# USB_Interlock_V3.net
KiCad netlist of a schematic drawn in EAGLE
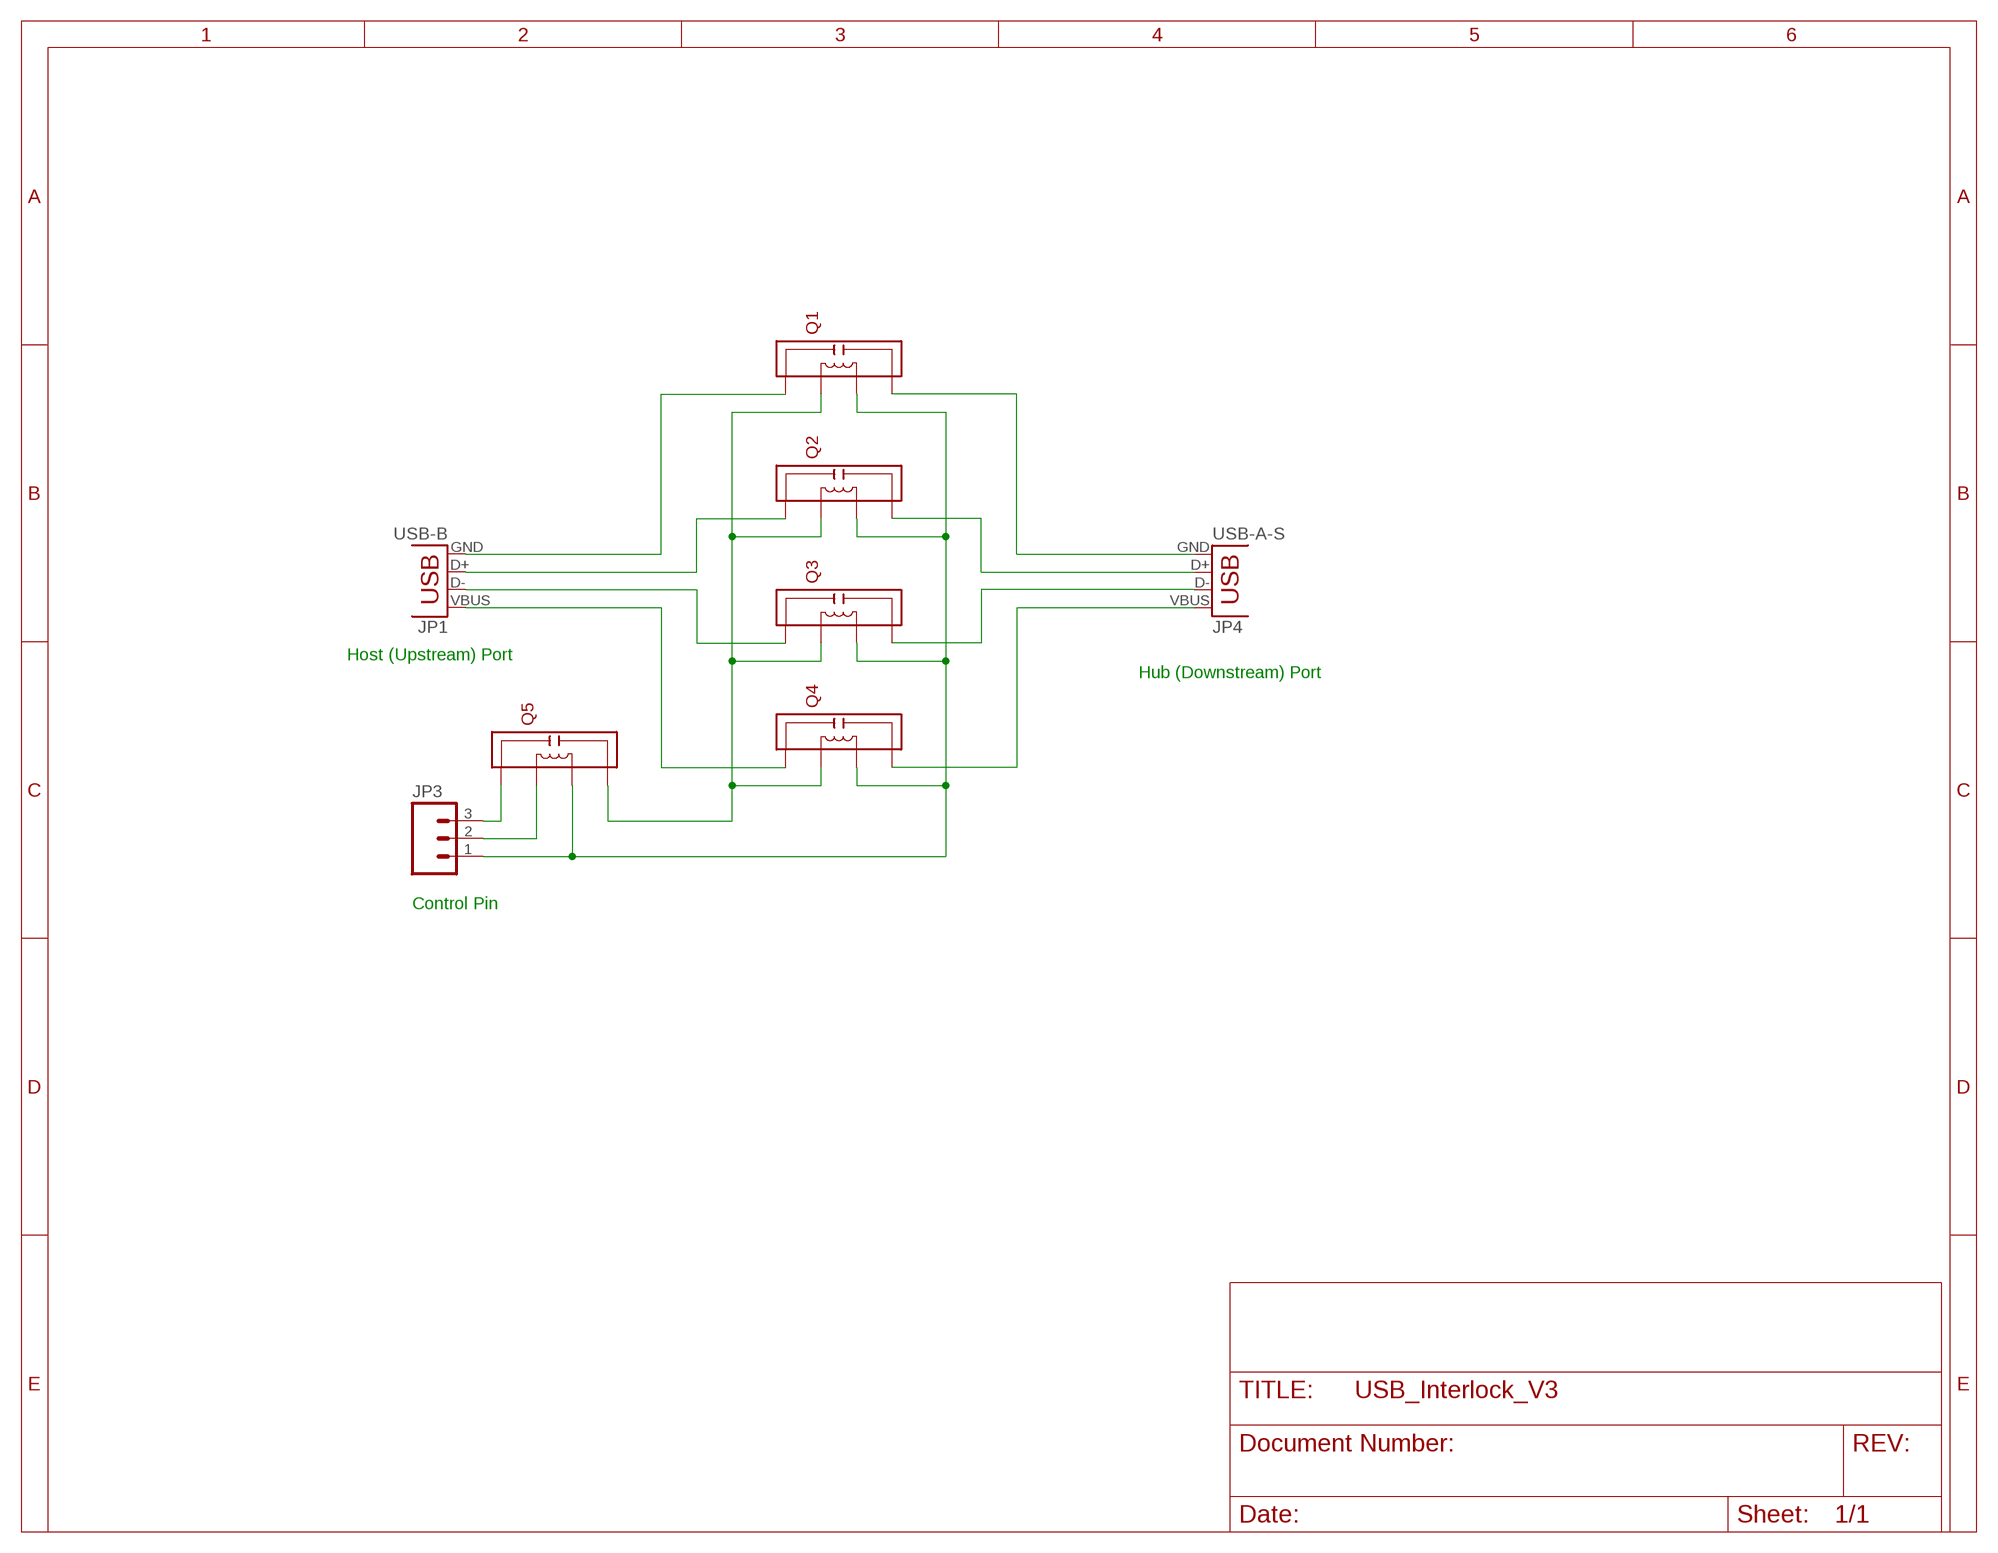
[diagram p0: schematic, sheet 1]

(export (version "E")
  (design (tool "Eeschema 10.0.6"))
  (components
    (comp (ref "JP1")
      (value "USB-B")
      (footprint "eagle-import:USB-B-PTH")
      (libsource (lib "eagle-import") (part "USBPTH"))
    )
    (comp (ref "JP3")
      (value "M03LONGPADS")
      (footprint "eagle-import:1X03_LONGPADS")
      (libsource (lib "eagle-import") (part "M03LONGPADS"))
    )
    (comp (ref "JP4")
      (value "USB-A-S")
      (footprint "eagle-import:USB-A-S")
      (libsource (lib "eagle-import") (part "USB-A-S"))
    )
    (comp (ref "Q1")
      (value "9007-12-01")
      (footprint "eagle-import:9007-12-01")
      (libsource (lib "eagle-import") (part "9007-12-01"))
    )
    (comp (ref "Q2")
      (value "9007-12-01")
      (footprint "eagle-import:9007-12-01")
      (libsource (lib "eagle-import") (part "9007-12-01"))
    )
    (comp (ref "Q3")
      (value "9007-12-01")
      (footprint "eagle-import:9007-12-01")
      (libsource (lib "eagle-import") (part "9007-12-01"))
    )
    (comp (ref "Q4")
      (value "9007-12-01")
      (footprint "eagle-import:9007-12-01")
      (libsource (lib "eagle-import") (part "9007-12-01"))
    )
    (comp (ref "Q5")
      (value "9007-12-01")
      (footprint "eagle-import:9007-12-01")
      (libsource (lib "eagle-import") (part "9007-12-01"))
    )
  )
  (nets
    (net (code "1") (name "Net-(JP1-PadD+)") (class "Default")
      (node (ref "JP1") (pin "D+") (pinfunction "D+_D+") (pintype "bidirectional"))
      (node (ref "Q2") (pin "P$1") (pinfunction "P$1_P$1") (pintype "bidirectional"))
    )
    (net (code "2") (name "Net-(JP1-PadD-)") (class "Default")
      (node (ref "JP1") (pin "D-") (pinfunction "D-_D-") (pintype "bidirectional"))
      (node (ref "Q3") (pin "P$1") (pinfunction "P$1_P$1") (pintype "bidirectional"))
    )
    (net (code "3") (name "Net-(JP1-PadGND)") (class "Default")
      (node (ref "JP1") (pin "GND") (pinfunction "GND_GND") (pintype "bidirectional"))
      (node (ref "Q1") (pin "P$1") (pinfunction "P$1_P$1") (pintype "bidirectional"))
    )
    (net (code "4") (name "Net-(JP1-PadVBUS)") (class "Default")
      (node (ref "JP1") (pin "VBUS") (pinfunction "VBUS_VBUS") (pintype "bidirectional"))
      (node (ref "Q4") (pin "P$1") (pinfunction "P$1_P$1") (pintype "bidirectional"))
    )
    (net (code "5") (name "Net-(JP3-Pad1)") (class "Default")
      (node (ref "JP3") (pin "1") (pinfunction "1_1") (pintype "passive"))
      (node (ref "Q1") (pin "P$3") (pinfunction "P$3_P$3") (pintype "output"))
      (node (ref "Q2") (pin "P$3") (pinfunction "P$3_P$3") (pintype "output"))
      (node (ref "Q3") (pin "P$3") (pinfunction "P$3_P$3") (pintype "output"))
      (node (ref "Q4") (pin "P$3") (pinfunction "P$3_P$3") (pintype "output"))
      (node (ref "Q5") (pin "P$3") (pinfunction "P$3_P$3") (pintype "output"))
    )
    (net (code "6") (name "Net-(JP3-Pad2)") (class "Default")
      (node (ref "JP3") (pin "2") (pinfunction "2_2") (pintype "passive"))
      (node (ref "Q5") (pin "P$2") (pinfunction "P$2_P$2") (pintype "input"))
    )
    (net (code "7") (name "Net-(JP3-Pad3)") (class "Default")
      (node (ref "JP3") (pin "3") (pinfunction "3_3") (pintype "passive"))
      (node (ref "Q5") (pin "P$1") (pinfunction "P$1_P$1") (pintype "bidirectional"))
    )
    (net (code "8") (name "Net-(JP4-PadD+)") (class "Default")
      (node (ref "JP4") (pin "D+") (pinfunction "D+_D+") (pintype "bidirectional"))
      (node (ref "Q2") (pin "P$4") (pinfunction "P$4_P$4") (pintype "bidirectional"))
    )
    (net (code "9") (name "Net-(JP4-PadD-)") (class "Default")
      (node (ref "JP4") (pin "D-") (pinfunction "D-_D-") (pintype "bidirectional"))
      (node (ref "Q3") (pin "P$4") (pinfunction "P$4_P$4") (pintype "bidirectional"))
    )
    (net (code "10") (name "Net-(JP4-PadGND)") (class "Default")
      (node (ref "JP4") (pin "GND") (pinfunction "GND_GND") (pintype "bidirectional"))
      (node (ref "Q1") (pin "P$4") (pinfunction "P$4_P$4") (pintype "bidirectional"))
    )
    (net (code "11") (name "Net-(JP4-PadVBUS)") (class "Default")
      (node (ref "JP4") (pin "VBUS") (pinfunction "VBUS_VBUS") (pintype "bidirectional"))
      (node (ref "Q4") (pin "P$4") (pinfunction "P$4_P$4") (pintype "bidirectional"))
    )
    (net (code "12") (name "Net-(Q1-PadP$2)") (class "Default")
      (node (ref "Q1") (pin "P$2") (pinfunction "P$2_P$2") (pintype "input"))
      (node (ref "Q2") (pin "P$2") (pinfunction "P$2_P$2") (pintype "input"))
      (node (ref "Q3") (pin "P$2") (pinfunction "P$2_P$2") (pintype "input"))
      (node (ref "Q4") (pin "P$2") (pinfunction "P$2_P$2") (pintype "input"))
      (node (ref "Q5") (pin "P$4") (pinfunction "P$4_P$4") (pintype "bidirectional"))
    )
  )
)
